# PWM_PPM_FMU_REV_1B.net
KiCad netlist of a schematic drawn in Altium Designer
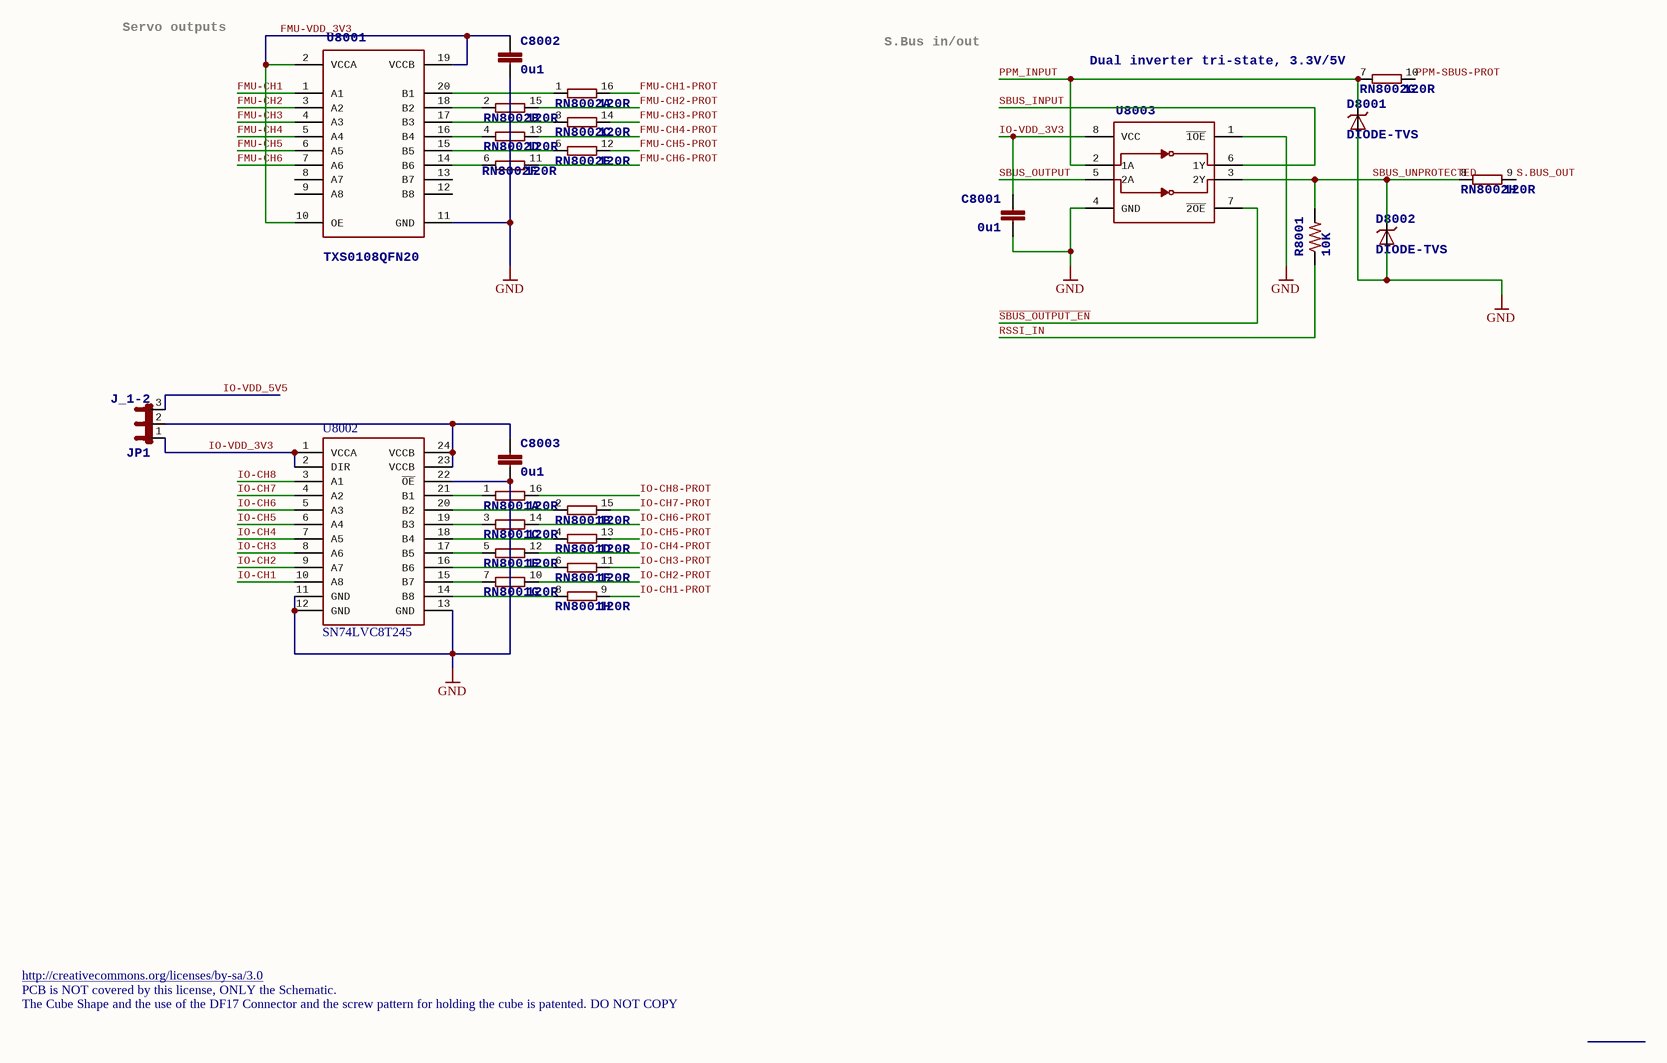
[diagram p0: PWM_PPM_FMU_REV_1B.SchDoc]

(export (version "E")
  (design (tool "Eeschema 10.0.6"))
  (components
    (comp (ref "C8001")
      (value "0u1")
      (footprint "0402-CAP")
      (description "CAP CER 0.1UF 16V Y5V 0402")
      (libsource (lib "") (part "CAP0402_1"))
    )
    (comp (ref "C8002")
      (value "0u1")
      (footprint "0402-CAP")
      (description "CAP CER 0.1UF 16V Y5V 0402")
      (libsource (lib "pixhawk2") (part "CAP0402"))
    )
    (comp (ref "C8003")
      (value "0u1")
      (footprint "0402-CAP")
      (description "CAP CER 0.1UF 16V Y5V 0402")
      (libsource (lib "pixhawk2") (part "CAP0402"))
    )
    (comp (ref "D8001")
      (value "DIODE-TVS")
      (footprint "0402-TVS")
      (description "TVS DIODE 14VWM 40VC 0402")
      (libsource (lib "pixhawk2") (part "DIODE-TVS"))
    )
    (comp (ref "D8002")
      (value "DIODE-TVS")
      (footprint "0402-TVS")
      (description "TVS DIODE 14VWM 40VC 0402")
      (libsource (lib "pixhawk2") (part "DIODE-TVS"))
    )
    (comp (ref "JP1")
      (value "J_1-2")
      (footprint "SJ_3_NO_PLACE_1-2_short")
      (libsource (lib "3DR") (part "JUMPER-31-2"))
    )
    (comp (ref "R8001")
      (value "10K")
      (footprint "0402-RES")
      (description "RES 10K OHM 1/16W 1% 0402 SMD")
      (libsource (lib "pixhawk2") (part "RESISTOR0402-RES"))
    )
    (comp (ref "RN8001")
      (value "120R")
      (footprint "EXB2HV")
      (description "RES ARRAY 120 OHM 8 RES 1506")
      (libsource (lib "pixhawk2") (part "8R-NEXB2HV-220R"))
    )
    (comp (ref "RN8002")
      (value "120R")
      (footprint "EXB2HV")
      (description "RES ARRAY 120 OHM 8 RES 1506")
      (libsource (lib "pixhawk2") (part "8R-NEXB2HV-220R"))
    )
    (comp (ref "U8001")
      (value "TXS0108QFN20")
      (footprint "QFN20-RGY")
      (description "IC XLATR VOLT-LVL 8B BDIR 20QFN")
      (libsource (lib "pixhawk2") (part "TXS0108QFN20"))
    )
    (comp (ref "U8002")
      (value "SN74LVC8T245")
      (footprint "QFN24-RGY")
      (libsource (lib "3DR") (part "SN74LVC8T245"))
    )
    (comp (ref "U8003")
      (value "Dual inverter tri-state, 3.3V/5V")
      (footprint "TSSOP8_SOT505-2")
      (description "IC INVERTER DUAL 4-INPUT 8TSSOP")
      (libsource (lib "pixhawk2") (part "74LVC2G240-TSSOP-8"))
    )
  )
  (nets
    (net (code "1") (name "/FMU-CH1") (class "Default")
      (node (ref "U8001") (pin "1") (pinfunction "A1_1") (pintype "passive"))
    )
    (net (code "2") (name "/FMU-CH1-PROT") (class "Default")
      (node (ref "RN8002") (pin "16") (pinfunction "2_16") (pintype "passive"))
    )
    (net (code "3") (name "/FMU-CH2") (class "Default")
      (node (ref "U8001") (pin "3") (pinfunction "A2_3") (pintype "passive"))
    )
    (net (code "4") (name "/FMU-CH2-PROT") (class "Default")
      (node (ref "RN8002") (pin "15") (pinfunction "2_15") (pintype "passive"))
    )
    (net (code "5") (name "/FMU-CH3") (class "Default")
      (node (ref "U8001") (pin "4") (pinfunction "A3_4") (pintype "passive"))
    )
    (net (code "6") (name "/FMU-CH3-PROT") (class "Default")
      (node (ref "RN8002") (pin "14") (pinfunction "2_14") (pintype "passive"))
    )
    (net (code "7") (name "/FMU-CH4") (class "Default")
      (node (ref "U8001") (pin "5") (pinfunction "A4_5") (pintype "passive"))
    )
    (net (code "8") (name "/FMU-CH4-PROT") (class "Default")
      (node (ref "RN8002") (pin "13") (pinfunction "2_13") (pintype "passive"))
    )
    (net (code "9") (name "/FMU-CH5") (class "Default")
      (node (ref "U8001") (pin "6") (pinfunction "A5_6") (pintype "passive"))
    )
    (net (code "10") (name "/FMU-CH5-PROT") (class "Default")
      (node (ref "RN8002") (pin "12") (pinfunction "2_12") (pintype "passive"))
    )
    (net (code "11") (name "/FMU-CH6") (class "Default")
      (node (ref "U8001") (pin "7") (pinfunction "A6_7") (pintype "passive"))
    )
    (net (code "12") (name "/FMU-CH6-PROT") (class "Default")
      (node (ref "RN8002") (pin "11") (pinfunction "2_11") (pintype "passive"))
    )
    (net (code "13") (name "/FMU-VDD_3V3") (class "Default")
      (node (ref "C8002") (pin "P$1") (pinfunction "1_P$1") (pintype "passive"))
      (node (ref "U8001") (pin "10") (pinfunction "OE_10") (pintype "passive"))
      (node (ref "U8001") (pin "19") (pinfunction "VCCB_19") (pintype "passive"))
      (node (ref "U8001") (pin "2") (pinfunction "VCCA_2") (pintype "passive"))
    )
    (net (code "14") (name "/IO-CH1") (class "Default")
      (node (ref "U8002") (pin "10") (pinfunction "A8_10") (pintype "passive"))
    )
    (net (code "15") (name "/IO-CH1-PROT") (class "Default")
      (node (ref "RN8001") (pin "9") (pinfunction "2_9") (pintype "passive"))
    )
    (net (code "16") (name "/IO-CH2") (class "Default")
      (node (ref "U8002") (pin "9") (pinfunction "A7_9") (pintype "passive"))
    )
    (net (code "17") (name "/IO-CH2-PROT") (class "Default")
      (node (ref "RN8001") (pin "10") (pinfunction "2_10") (pintype "passive"))
    )
    (net (code "18") (name "/IO-CH3") (class "Default")
      (node (ref "U8002") (pin "8") (pinfunction "A6_8") (pintype "passive"))
    )
    (net (code "19") (name "/IO-CH3-PROT") (class "Default")
      (node (ref "RN8001") (pin "11") (pinfunction "2_11") (pintype "passive"))
    )
    (net (code "20") (name "/IO-CH4") (class "Default")
      (node (ref "U8002") (pin "7") (pinfunction "A5_7") (pintype "passive"))
    )
    (net (code "21") (name "/IO-CH4-PROT") (class "Default")
      (node (ref "RN8001") (pin "12") (pinfunction "2_12") (pintype "passive"))
    )
    (net (code "22") (name "/IO-CH5") (class "Default")
      (node (ref "U8002") (pin "6") (pinfunction "A4_6") (pintype "passive"))
    )
    (net (code "23") (name "/IO-CH5-PROT") (class "Default")
      (node (ref "RN8001") (pin "13") (pinfunction "2_13") (pintype "passive"))
    )
    (net (code "24") (name "/IO-CH6") (class "Default")
      (node (ref "U8002") (pin "5") (pinfunction "A3_5") (pintype "passive"))
    )
    (net (code "25") (name "/IO-CH6-PROT") (class "Default")
      (node (ref "RN8001") (pin "14") (pinfunction "2_14") (pintype "passive"))
    )
    (net (code "26") (name "/IO-CH7") (class "Default")
      (node (ref "U8002") (pin "4") (pinfunction "A2_4") (pintype "passive"))
    )
    (net (code "27") (name "/IO-CH7-PROT") (class "Default")
      (node (ref "RN8001") (pin "15") (pinfunction "2_15") (pintype "passive"))
    )
    (net (code "28") (name "/IO-CH8") (class "Default")
      (node (ref "U8002") (pin "3") (pinfunction "A1_3") (pintype "passive"))
    )
    (net (code "29") (name "/IO-CH8-PROT") (class "Default")
      (node (ref "RN8001") (pin "16") (pinfunction "2_16") (pintype "passive"))
    )
    (net (code "30") (name "/IO-VDD_3V3") (class "Default")
      (node (ref "C8001") (pin "P$1") (pinfunction "1_P$1") (pintype "passive"))
      (node (ref "JP1") (pin "1") (pinfunction "1_1") (pintype "passive"))
      (node (ref "U8002") (pin "1") (pinfunction "VCCA_1") (pintype "passive"))
      (node (ref "U8002") (pin "2") (pinfunction "DIR_2") (pintype "passive"))
      (node (ref "U8003") (pin "8") (pinfunction "VCC_8") (pintype "open_emitter"))
    )
    (net (code "31") (name "/IO-VDD_5V5") (class "Default")
      (node (ref "JP1") (pin "3") (pinfunction "3_3") (pintype "passive"))
    )
    (net (code "32") (name "/PPM-SBUS-PROT") (class "Default")
      (node (ref "RN8002") (pin "10") (pinfunction "2_10") (pintype "passive"))
    )
    (net (code "33") (name "/PPM_INPUT") (class "Default")
      (node (ref "D8001") (pin "C") (pinfunction "C_C") (pintype "passive"))
      (node (ref "RN8002") (pin "7") (pinfunction "1_7") (pintype "passive"))
      (node (ref "U8003") (pin "2") (pinfunction "1A_2") (pintype "passive"))
    )
    (net (code "34") (name "/RSSI_IN") (class "Default")
      (node (ref "R8001") (pin "P$1") (pinfunction "1_P$1") (pintype "passive"))
    )
    (net (code "35") (name "/S.BUS_OUT") (class "Default")
      (node (ref "RN8002") (pin "9") (pinfunction "2_9") (pintype "passive"))
    )
    (net (code "36") (name "/SBUS_INPUT") (class "Default")
      (node (ref "U8003") (pin "6") (pinfunction "1Y_6") (pintype "passive"))
    )
    (net (code "37") (name "/SBUS_OUTPUT") (class "Default")
      (node (ref "U8003") (pin "5") (pinfunction "2A_5") (pintype "passive"))
    )
    (net (code "38") (name "/SBUS_UNPROTECTED") (class "Default")
      (node (ref "D8002") (pin "C") (pinfunction "C_C") (pintype "passive"))
      (node (ref "R8001") (pin "P$2") (pinfunction "2_P$2") (pintype "passive"))
      (node (ref "RN8002") (pin "8") (pinfunction "1_8") (pintype "passive"))
      (node (ref "U8003") (pin "3") (pinfunction "2Y_3") (pintype "passive"))
    )
    (net (code "39") (name "/~{SBUS_OUTPUT_EN}") (class "Default")
      (node (ref "U8003") (pin "7") (pinfunction "~{2OE}_7") (pintype "passive"))
    )
    (net (code "40") (name "GND") (class "Default")
      (node (ref "C8001") (pin "P$2") (pinfunction "2_P$2") (pintype "passive"))
      (node (ref "C8002") (pin "P$2") (pinfunction "2_P$2") (pintype "passive"))
      (node (ref "C8003") (pin "P$2") (pinfunction "2_P$2") (pintype "passive"))
      (node (ref "D8001") (pin "A") (pinfunction "A_A") (pintype "passive"))
      (node (ref "D8002") (pin "A") (pinfunction "A_A") (pintype "passive"))
      (node (ref "U8001") (pin "11") (pinfunction "GND_11") (pintype "open_emitter"))
      (node (ref "U8002") (pin "11") (pinfunction "GND_11") (pintype "open_emitter"))
      (node (ref "U8002") (pin "12") (pinfunction "GND_12") (pintype "open_emitter"))
      (node (ref "U8002") (pin "13") (pinfunction "GND_13") (pintype "open_emitter"))
      (node (ref "U8002") (pin "22") (pinfunction "~{OE}_22") (pintype "passive"))
      (node (ref "U8003") (pin "1") (pinfunction "~{1OE}_1") (pintype "passive"))
      (node (ref "U8003") (pin "4") (pinfunction "GND_4") (pintype "open_emitter"))
    )
    (net (code "41") (name "Net-(C8003-1)") (class "Default")
      (node (ref "C8003") (pin "P$1") (pinfunction "1_P$1") (pintype "passive"))
      (node (ref "JP1") (pin "2") (pinfunction "2_2") (pintype "passive"))
      (node (ref "U8002") (pin "23") (pinfunction "VCCB_23") (pintype "passive"))
      (node (ref "U8002") (pin "24") (pinfunction "VCCB_24") (pintype "passive"))
    )
    (net (code "42") (name "Net-(RN8001B-1)") (class "Default")
      (node (ref "RN8001") (pin "2") (pinfunction "1_2") (pintype "passive"))
      (node (ref "U8002") (pin "20") (pinfunction "B2_20") (pintype "passive"))
    )
    (net (code "43") (name "Net-(RN8001C-1)") (class "Default")
      (node (ref "RN8001") (pin "3") (pinfunction "1_3") (pintype "passive"))
      (node (ref "U8002") (pin "19") (pinfunction "B3_19") (pintype "passive"))
    )
    (net (code "44") (name "Net-(RN8001D-1)") (class "Default")
      (node (ref "RN8001") (pin "4") (pinfunction "1_4") (pintype "passive"))
      (node (ref "U8002") (pin "18") (pinfunction "B4_18") (pintype "passive"))
    )
    (net (code "45") (name "Net-(RN8001E-1)") (class "Default")
      (node (ref "RN8001") (pin "5") (pinfunction "1_5") (pintype "passive"))
      (node (ref "U8002") (pin "17") (pinfunction "B5_17") (pintype "passive"))
    )
    (net (code "46") (name "Net-(RN8001F-1)") (class "Default")
      (node (ref "RN8001") (pin "6") (pinfunction "1_6") (pintype "passive"))
      (node (ref "U8002") (pin "16") (pinfunction "B6_16") (pintype "passive"))
    )
    (net (code "47") (name "Net-(RN8001G-1)") (class "Default")
      (node (ref "RN8001") (pin "7") (pinfunction "1_7") (pintype "passive"))
      (node (ref "U8002") (pin "15") (pinfunction "B7_15") (pintype "passive"))
    )
    (net (code "48") (name "Net-(RN8001H-1)") (class "Default")
      (node (ref "RN8001") (pin "8") (pinfunction "1_8") (pintype "passive"))
      (node (ref "U8002") (pin "14") (pinfunction "B8_14") (pintype "passive"))
    )
    (net (code "49") (name "Net-(RN8002B-1)") (class "Default")
      (node (ref "RN8002") (pin "2") (pinfunction "1_2") (pintype "passive"))
      (node (ref "U8001") (pin "18") (pinfunction "B2_18") (pintype "passive"))
    )
    (net (code "50") (name "Net-(RN8002C-1)") (class "Default")
      (node (ref "RN8002") (pin "3") (pinfunction "1_3") (pintype "passive"))
      (node (ref "U8001") (pin "17") (pinfunction "B3_17") (pintype "passive"))
    )
    (net (code "51") (name "Net-(RN8002D-1)") (class "Default")
      (node (ref "RN8002") (pin "4") (pinfunction "1_4") (pintype "passive"))
      (node (ref "U8001") (pin "16") (pinfunction "B4_16") (pintype "passive"))
    )
    (net (code "52") (name "Net-(RN8002E-1)") (class "Default")
      (node (ref "RN8002") (pin "5") (pinfunction "1_5") (pintype "passive"))
      (node (ref "U8001") (pin "15") (pinfunction "B5_15") (pintype "passive"))
    )
    (net (code "53") (name "Net-(RN8002F-1)") (class "Default")
      (node (ref "RN8002") (pin "6") (pinfunction "1_6") (pintype "passive"))
      (node (ref "U8001") (pin "14") (pinfunction "B6_14") (pintype "passive"))
    )
    (net (code "54") (name "Net-(U8001-B1)") (class "Default")
      (node (ref "RN8002") (pin "1") (pinfunction "1_1") (pintype "passive"))
      (node (ref "U8001") (pin "20") (pinfunction "B1_20") (pintype "passive"))
    )
    (net (code "55") (name "Net-(U8002-B1)") (class "Default")
      (node (ref "RN8001") (pin "1") (pinfunction "1_1") (pintype "passive"))
      (node (ref "U8002") (pin "21") (pinfunction "B1_21") (pintype "passive"))
    )
    (net (code "56") (name "unconnected-(U8001-A7-Pad8)") (class "Default")
      (node (ref "U8001") (pin "8") (pinfunction "A7_8") (pintype "passive"))
    )
    (net (code "57") (name "unconnected-(U8001-A8-Pad9)") (class "Default")
      (node (ref "U8001") (pin "9") (pinfunction "A8_9") (pintype "passive"))
    )
    (net (code "58") (name "unconnected-(U8001-B7-Pad13)") (class "Default")
      (node (ref "U8001") (pin "13") (pinfunction "B7_13") (pintype "passive"))
    )
    (net (code "59") (name "unconnected-(U8001-B8-Pad12)") (class "Default")
      (node (ref "U8001") (pin "12") (pinfunction "B8_12") (pintype "passive"))
    )
  )
)
